# adaptor2.net
KiCad netlist of a schematic drawn in EAGLE
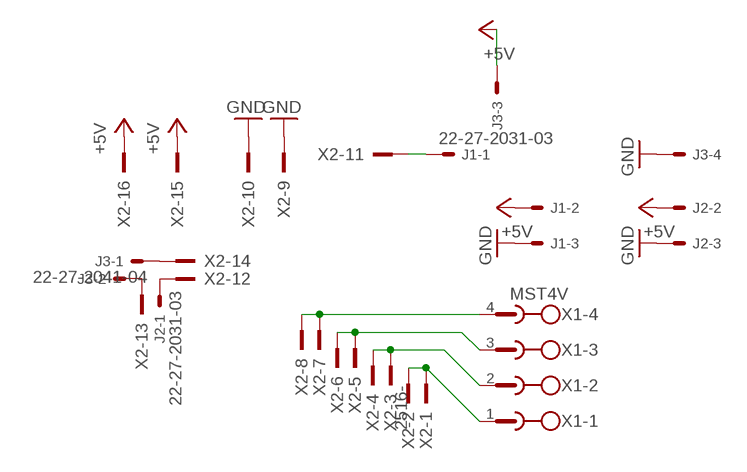
[diagram p0: schematic, sheet 1]

(export (version "E")
  (design (tool "Eeschema 10.0.6"))
  (components
    (comp (ref "J1")
      (value "22-27-2031-03")
      (footprint "eagle-import:6410-03")
      (libsource (lib "eagle-import") (part "22-?-0327-2031"))
    )
    (comp (ref "J2")
      (value "22-27-2031-03")
      (footprint "eagle-import:6410-03")
      (libsource (lib "eagle-import") (part "22-?-0327-2031"))
    )
    (comp (ref "J3")
      (value "22-27-2041-04")
      (footprint "eagle-import:6410-04")
      (libsource (lib "eagle-import") (part "22-?-0427-2041"))
    )
    (comp (ref "X1")
      (value "MST4V")
      (footprint "eagle-import:MSTBV4")
      (libsource (lib "eagle-import") (part "MST4V"))
    )
    (comp (ref "X2")
      (value "2516-")
      (footprint "eagle-import:PAK100_2500-16")
      (libsource (lib "eagle-import") (part "2516-"))
    )
  )
  (nets
    (net (code "1") (name "+5V") (class "Default")
      (node (ref "J1") (pin "2") (pinfunction "S_2") (pintype "passive"))
      (node (ref "J2") (pin "2") (pinfunction "S_2") (pintype "passive"))
      (node (ref "J3") (pin "3") (pinfunction "S_3") (pintype "passive"))
      (node (ref "X2") (pin "15") (pinfunction "KL_15") (pintype "passive"))
      (node (ref "X2") (pin "16") (pinfunction "KL_16") (pintype "passive"))
    )
    (net (code "2") (name "GND") (class "Default")
      (node (ref "J1") (pin "3") (pinfunction "S_3") (pintype "passive"))
      (node (ref "J2") (pin "3") (pinfunction "S_3") (pintype "passive"))
      (node (ref "J3") (pin "4") (pinfunction "S_4") (pintype "passive"))
      (node (ref "X2") (pin "10") (pinfunction "KL_10") (pintype "passive"))
      (node (ref "X2") (pin "9") (pinfunction "KL_9") (pintype "passive"))
    )
    (net (code "3") (name "Net-(J1A-S)") (class "Default")
      (node (ref "J1") (pin "1") (pinfunction "S_1") (pintype "passive"))
      (node (ref "X2") (pin "11") (pinfunction "KL_11") (pintype "passive"))
    )
    (net (code "4") (name "Net-(J2A-S)") (class "Default")
      (node (ref "J2") (pin "1") (pinfunction "S_1") (pintype "passive"))
      (node (ref "X2") (pin "12") (pinfunction "KL_12") (pintype "passive"))
    )
    (net (code "5") (name "Net-(J3A-S)") (class "Default")
      (node (ref "J3") (pin "1") (pinfunction "S_1") (pintype "passive"))
      (node (ref "X2") (pin "14") (pinfunction "KL_14") (pintype "passive"))
    )
    (net (code "6") (name "Net-(J3B-S)") (class "Default")
      (node (ref "J3") (pin "2") (pinfunction "S_2") (pintype "passive"))
      (node (ref "X2") (pin "13") (pinfunction "KL_13") (pintype "passive"))
    )
    (net (code "7") (name "Net-(X1B-1)") (class "Default")
      (node (ref "X1") (pin "2") (pinfunction "1_2") (pintype "passive"))
      (node (ref "X2") (pin "3") (pinfunction "KL_3") (pintype "passive"))
      (node (ref "X2") (pin "4") (pinfunction "KL_4") (pintype "passive"))
    )
    (net (code "8") (name "Net-(X1C-1)") (class "Default")
      (node (ref "X1") (pin "3") (pinfunction "1_3") (pintype "passive"))
      (node (ref "X2") (pin "5") (pinfunction "KL_5") (pintype "passive"))
      (node (ref "X2") (pin "6") (pinfunction "KL_6") (pintype "passive"))
    )
    (net (code "9") (name "Net-(X1D-1)") (class "Default")
      (node (ref "X1") (pin "4") (pinfunction "1_4") (pintype "passive"))
      (node (ref "X2") (pin "7") (pinfunction "KL_7") (pintype "passive"))
      (node (ref "X2") (pin "8") (pinfunction "KL_8") (pintype "passive"))
    )
    (net (code "10") (name "Net-(X2A-KL)") (class "Default")
      (node (ref "X1") (pin "1") (pinfunction "1_1") (pintype "passive"))
      (node (ref "X2") (pin "1") (pinfunction "KL_1") (pintype "passive"))
      (node (ref "X2") (pin "2") (pinfunction "KL_2") (pintype "passive"))
    )
  )
)
